# 1_WM-N400MSE.net
KiCad netlist of a schematic drawn in Altium Designer
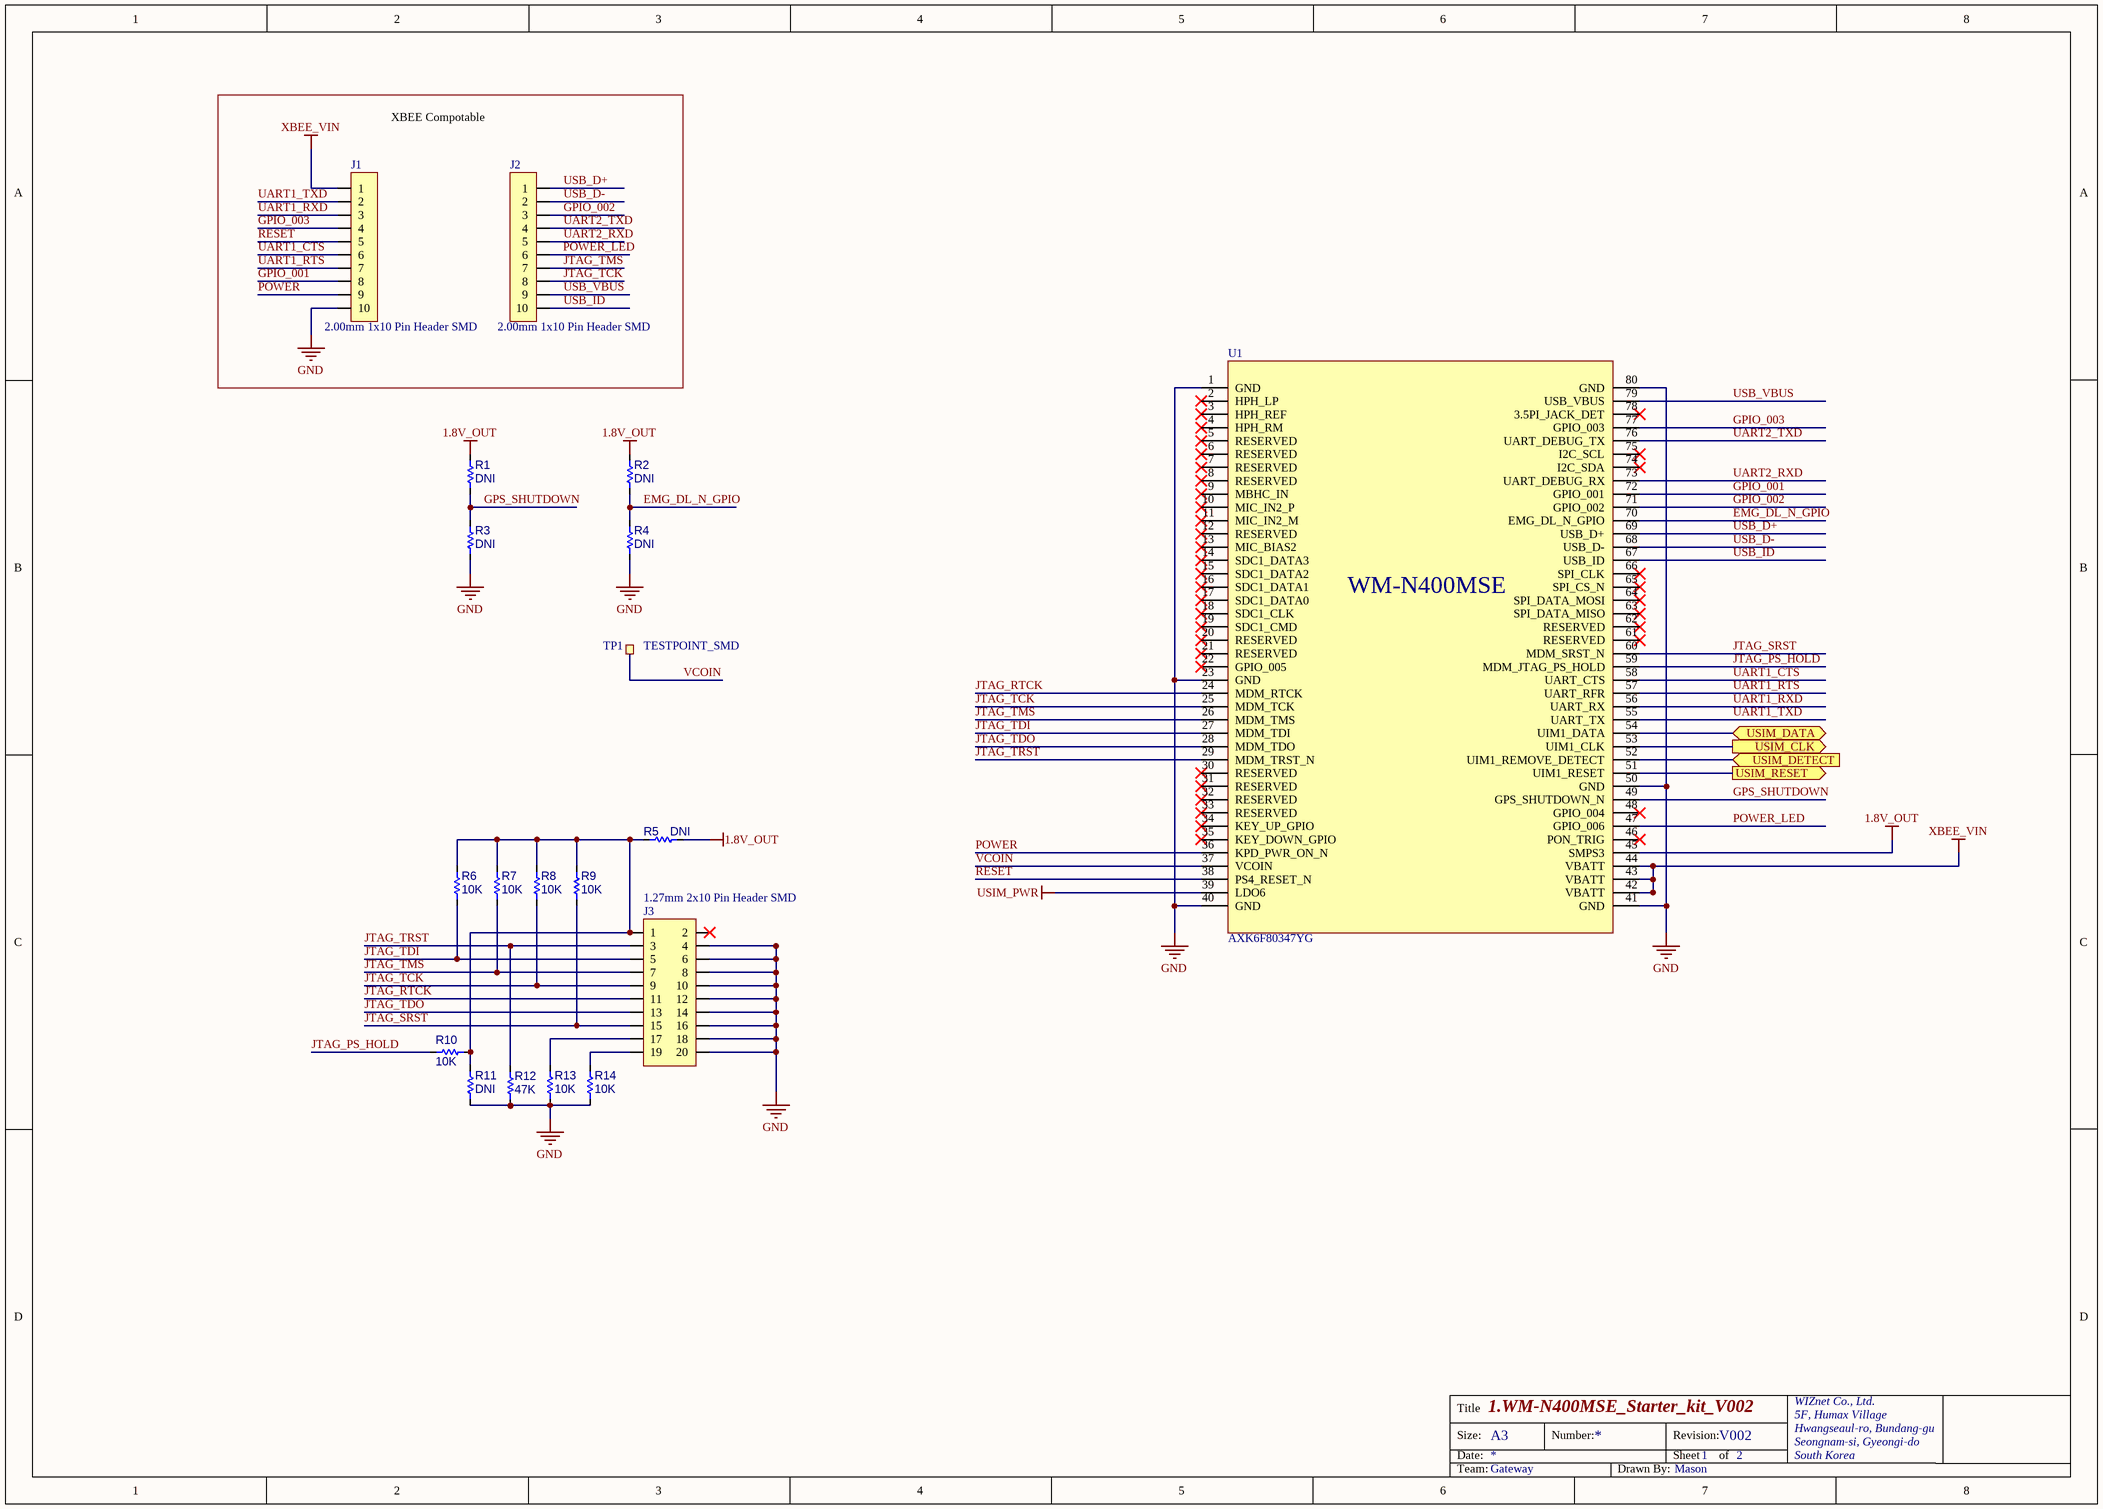
[diagram p0: 1.WM-N400MSE.SchDoc]

(export (version "E")
  (design (tool "Eeschema 10.0.6"))
  (components
    (comp (ref "J1")
      (value "2.00mm 1x10 Pin Header SMD")
      (footprint "IDC(SMD)-1X10(2MM)")
      (libsource (lib "Scott_lib") (part "2.00mm 1x10 Pin Header SMD"))
    )
    (comp (ref "J2")
      (value "2.00mm 1x10 Pin Header SMD")
      (footprint "IDC(SMD)-1X10(2MM)")
      (libsource (lib "") (part "2.00mm 1x10 Pin Header SMD_1"))
    )
    (comp (ref "J3")
      (value "1.27mm 2x10 Pin Header SMD")
      (footprint "IDC(SMD)-2X10(1.27MM)")
      (libsource (lib "Scott_lib") (part "1.27mm 2x10 Pin Header SMD"))
    )
    (comp (ref "R1")
      (value "DNI")
      (footprint "RES-0402")
      (description "RES-0402")
      (libsource (lib "Scott_lib") (part "RES-0402"))
    )
    (comp (ref "R2")
      (value "DNI")
      (footprint "RES-0402")
      (description "RES-0402")
      (libsource (lib "Scott_lib") (part "RES-0402"))
    )
    (comp (ref "R3")
      (value "DNI")
      (footprint "RES-0402")
      (description "RES-0402")
      (libsource (lib "Scott_lib") (part "RES-0402"))
    )
    (comp (ref "R4")
      (value "DNI")
      (footprint "RES-0402")
      (description "RES-0402")
      (libsource (lib "Scott_lib") (part "RES-0402"))
    )
    (comp (ref "R5")
      (value "DNI")
      (footprint "RES-0402")
      (description "RES-0402")
      (libsource (lib "Scott_lib") (part "RES-0402"))
    )
    (comp (ref "R6")
      (value "10K")
      (footprint "RES-0402")
      (description "RES-0402")
      (libsource (lib "Scott_lib") (part "RES-0402"))
    )
    (comp (ref "R7")
      (value "10K")
      (footprint "RES-0402")
      (description "RES-0402")
      (libsource (lib "Scott_lib") (part "RES-0402"))
    )
    (comp (ref "R8")
      (value "10K")
      (footprint "RES-0402")
      (description "RES-0402")
      (libsource (lib "Scott_lib") (part "RES-0402"))
    )
    (comp (ref "R9")
      (value "10K")
      (footprint "RES-0402")
      (description "RES-0402")
      (libsource (lib "Scott_lib") (part "RES-0402"))
    )
    (comp (ref "R10")
      (value "10K")
      (footprint "RES-0402")
      (description "RES-0402")
      (libsource (lib "Scott_lib") (part "RES-0402"))
    )
    (comp (ref "R11")
      (value "DNI")
      (footprint "RES-0402")
      (description "RES-0402")
      (libsource (lib "Scott_lib") (part "RES-0402"))
    )
    (comp (ref "R12")
      (value "47K")
      (footprint "RES-0402")
      (description "RES-0402")
      (libsource (lib "Scott_lib") (part "RES-0402"))
    )
    (comp (ref "R13")
      (value "10K")
      (footprint "RES-0402")
      (description "RES-0402")
      (libsource (lib "Scott_lib") (part "RES-0402"))
    )
    (comp (ref "R14")
      (value "10K")
      (footprint "RES-0402")
      (description "RES-0402")
      (libsource (lib "Scott_lib") (part "RES-0402"))
    )
    (comp (ref "TP1")
      (value "TESTPOINT_SMD")
      (footprint "TP(SMD)-1PI")
      (description "TEST POINT")
      (libsource (lib "Scott_lib") (part "TESTPOINT_SMD"))
    )
    (comp (ref "U1")
      (value "AXK6F80347YG")
      (footprint "WM-N400MSE")
      (description "WM-N400MSE")
      (libsource (lib "Mason_lib") (part "WM-N400MSE"))
    )
  )
  (nets
    (net (code "1") (name "/EMG_DL_N_GPIO") (class "Default")
      (node (ref "R2") (pin "1") (pinfunction "1_1") (pintype "passive"))
      (node (ref "R4") (pin "2") (pinfunction "2_2") (pintype "passive"))
      (node (ref "U1") (pin "70") (pinfunction "EMG_DL_N_GPIO_70") (pintype "passive"))
    )
    (net (code "2") (name "/GPIO_001") (class "Default")
      (node (ref "J1") (pin "8") (pinfunction "8_8") (pintype "passive"))
      (node (ref "U1") (pin "72") (pinfunction "GPIO_001_72") (pintype "passive"))
    )
    (net (code "3") (name "/GPIO_002") (class "Default")
      (node (ref "J2") (pin "3") (pinfunction "3_3") (pintype "passive"))
      (node (ref "U1") (pin "71") (pinfunction "GPIO_002_71") (pintype "passive"))
    )
    (net (code "4") (name "/GPIO_003") (class "Default")
      (node (ref "J1") (pin "4") (pinfunction "4_4") (pintype "passive"))
      (node (ref "U1") (pin "77") (pinfunction "GPIO_003_77") (pintype "passive"))
    )
    (net (code "5") (name "/GPS_SHUTDOWN") (class "Default")
      (node (ref "R1") (pin "1") (pinfunction "1_1") (pintype "passive"))
      (node (ref "R3") (pin "2") (pinfunction "2_2") (pintype "passive"))
      (node (ref "U1") (pin "49") (pinfunction "GPS_SHUTDOWN_N_49") (pintype "passive"))
    )
    (net (code "6") (name "/JTAG_PS_HOLD") (class "Default")
      (node (ref "R10") (pin "2") (pinfunction "2_2") (pintype "passive"))
      (node (ref "U1") (pin "59") (pinfunction "MDM_JTAG_PS_HOLD_59") (pintype "passive"))
    )
    (net (code "7") (name "/JTAG_RTCK") (class "Default")
      (node (ref "J3") (pin "11") (pinfunction "11_11") (pintype "passive"))
      (node (ref "U1") (pin "24") (pinfunction "MDM_RTCK_24") (pintype "passive"))
    )
    (net (code "8") (name "/JTAG_SRST") (class "Default")
      (node (ref "J3") (pin "15") (pinfunction "15_15") (pintype "passive"))
      (node (ref "R9") (pin "1") (pinfunction "1_1") (pintype "passive"))
      (node (ref "U1") (pin "60") (pinfunction "MDM_SRST_N_60") (pintype "passive"))
    )
    (net (code "9") (name "/JTAG_TCK") (class "Default")
      (node (ref "J2") (pin "8") (pinfunction "8_8") (pintype "passive"))
      (node (ref "J3") (pin "9") (pinfunction "9_9") (pintype "passive"))
      (node (ref "R8") (pin "1") (pinfunction "1_1") (pintype "passive"))
      (node (ref "U1") (pin "25") (pinfunction "MDM_TCK_25") (pintype "passive"))
    )
    (net (code "10") (name "/JTAG_TDI") (class "Default")
      (node (ref "J3") (pin "5") (pinfunction "5_5") (pintype "passive"))
      (node (ref "R6") (pin "1") (pinfunction "1_1") (pintype "passive"))
      (node (ref "U1") (pin "27") (pinfunction "MDM_TDI_27") (pintype "passive"))
    )
    (net (code "11") (name "/JTAG_TDO") (class "Default")
      (node (ref "J3") (pin "13") (pinfunction "13_13") (pintype "passive"))
      (node (ref "U1") (pin "28") (pinfunction "MDM_TDO_28") (pintype "passive"))
    )
    (net (code "12") (name "/JTAG_TMS") (class "Default")
      (node (ref "J2") (pin "7") (pinfunction "7_7") (pintype "passive"))
      (node (ref "J3") (pin "7") (pinfunction "7_7") (pintype "passive"))
      (node (ref "R7") (pin "1") (pinfunction "1_1") (pintype "passive"))
      (node (ref "U1") (pin "26") (pinfunction "MDM_TMS_26") (pintype "passive"))
    )
    (net (code "13") (name "/JTAG_TRST") (class "Default")
      (node (ref "J3") (pin "3") (pinfunction "3_3") (pintype "passive"))
      (node (ref "R12") (pin "2") (pinfunction "2_2") (pintype "passive"))
      (node (ref "U1") (pin "29") (pinfunction "MDM_TRST_N_29") (pintype "passive"))
    )
    (net (code "14") (name "/POWER") (class "Default")
      (node (ref "J1") (pin "9") (pinfunction "9_9") (pintype "passive"))
      (node (ref "U1") (pin "36") (pinfunction "KPD_PWR_ON_N_36") (pintype "passive"))
    )
    (net (code "15") (name "/POWER_LED") (class "Default")
      (node (ref "J2") (pin "6") (pinfunction "6_6") (pintype "passive"))
      (node (ref "U1") (pin "47") (pinfunction "GPIO_006_47") (pintype "passive"))
    )
    (net (code "16") (name "/RESET") (class "Default")
      (node (ref "J1") (pin "5") (pinfunction "5_5") (pintype "passive"))
      (node (ref "U1") (pin "38") (pinfunction "PS4_RESET_N_38") (pintype "passive"))
    )
    (net (code "17") (name "/UART1_CTS") (class "Default")
      (node (ref "J1") (pin "6") (pinfunction "6_6") (pintype "passive"))
      (node (ref "U1") (pin "58") (pinfunction "UART_CTS_58") (pintype "passive"))
    )
    (net (code "18") (name "/UART1_RTS") (class "Default")
      (node (ref "J1") (pin "7") (pinfunction "7_7") (pintype "passive"))
      (node (ref "U1") (pin "57") (pinfunction "UART_RFR_57") (pintype "passive"))
    )
    (net (code "19") (name "/UART1_RXD") (class "Default")
      (node (ref "J1") (pin "3") (pinfunction "3_3") (pintype "passive"))
      (node (ref "U1") (pin "56") (pinfunction "UART_RX_56") (pintype "passive"))
    )
    (net (code "20") (name "/UART1_TXD") (class "Default")
      (node (ref "J1") (pin "2") (pinfunction "2_2") (pintype "passive"))
      (node (ref "U1") (pin "55") (pinfunction "UART_TX_55") (pintype "passive"))
    )
    (net (code "21") (name "/UART2_RXD") (class "Default")
      (node (ref "J2") (pin "5") (pinfunction "5_5") (pintype "passive"))
      (node (ref "U1") (pin "73") (pinfunction "UART_DEBUG_RX_73") (pintype "passive"))
    )
    (net (code "22") (name "/UART2_TXD") (class "Default")
      (node (ref "J2") (pin "4") (pinfunction "4_4") (pintype "passive"))
      (node (ref "U1") (pin "76") (pinfunction "UART_DEBUG_TX_76") (pintype "passive"))
    )
    (net (code "23") (name "/USB_D+") (class "Default")
      (node (ref "J2") (pin "1") (pinfunction "1_1") (pintype "passive"))
      (node (ref "U1") (pin "69") (pinfunction "USB_D+_69") (pintype "passive"))
    )
    (net (code "24") (name "/USB_D-") (class "Default")
      (node (ref "J2") (pin "2") (pinfunction "2_2") (pintype "passive"))
      (node (ref "U1") (pin "68") (pinfunction "USB_D-_68") (pintype "passive"))
    )
    (net (code "25") (name "/USB_ID") (class "Default")
      (node (ref "J2") (pin "10") (pinfunction "10_10") (pintype "passive"))
      (node (ref "U1") (pin "67") (pinfunction "USB_ID_67") (pintype "passive"))
    )
    (net (code "26") (name "/USB_VBUS") (class "Default")
      (node (ref "J2") (pin "9") (pinfunction "9_9") (pintype "passive"))
      (node (ref "U1") (pin "79") (pinfunction "USB_VBUS_79") (pintype "passive"))
    )
    (net (code "27") (name "/USIM_CLK") (class "Default")
      (node (ref "U1") (pin "53") (pinfunction "UIM1_CLK_53") (pintype "passive"))
    )
    (net (code "28") (name "/USIM_DATA") (class "Default")
      (node (ref "U1") (pin "54") (pinfunction "UIM1_DATA_54") (pintype "passive"))
    )
    (net (code "29") (name "/USIM_DETECT") (class "Default")
      (node (ref "U1") (pin "52") (pinfunction "UIM1_REMOVE_DETECT_52") (pintype "passive"))
    )
    (net (code "30") (name "/USIM_RESET") (class "Default")
      (node (ref "U1") (pin "51") (pinfunction "UIM1_RESET_51") (pintype "passive"))
    )
    (net (code "31") (name "/VCOIN") (class "Default")
      (node (ref "TP1") (pin "1") (pinfunction "TETSPOINT_1") (pintype "passive"))
      (node (ref "U1") (pin "37") (pinfunction "VCOIN_37") (pintype "passive"))
    )
    (net (code "32") (name "1.8V_OUT") (class "Default")
      (node (ref "R1") (pin "2") (pinfunction "2_2") (pintype "passive"))
      (node (ref "R2") (pin "2") (pinfunction "2_2") (pintype "passive"))
      (node (ref "R5") (pin "1") (pinfunction "1_1") (pintype "passive"))
      (node (ref "U1") (pin "45") (pinfunction "SMPS3_45") (pintype "passive"))
    )
    (net (code "33") (name "GND") (class "Default")
      (node (ref "J1") (pin "10") (pinfunction "10_10") (pintype "passive"))
      (node (ref "J3") (pin "10") (pinfunction "10_10") (pintype "passive"))
      (node (ref "J3") (pin "12") (pinfunction "12_12") (pintype "passive"))
      (node (ref "J3") (pin "14") (pinfunction "14_14") (pintype "passive"))
      (node (ref "J3") (pin "16") (pinfunction "16_16") (pintype "passive"))
      (node (ref "J3") (pin "18") (pinfunction "18_18") (pintype "passive"))
      (node (ref "J3") (pin "20") (pinfunction "20_20") (pintype "passive"))
      (node (ref "J3") (pin "4") (pinfunction "4_4") (pintype "passive"))
      (node (ref "J3") (pin "6") (pinfunction "6_6") (pintype "passive"))
      (node (ref "J3") (pin "8") (pinfunction "8_8") (pintype "passive"))
      (node (ref "R11") (pin "1") (pinfunction "1_1") (pintype "passive"))
      (node (ref "R12") (pin "1") (pinfunction "1_1") (pintype "passive"))
      (node (ref "R13") (pin "1") (pinfunction "1_1") (pintype "passive"))
      (node (ref "R14") (pin "1") (pinfunction "1_1") (pintype "passive"))
      (node (ref "R3") (pin "1") (pinfunction "1_1") (pintype "passive"))
      (node (ref "R4") (pin "1") (pinfunction "1_1") (pintype "passive"))
      (node (ref "U1") (pin "1") (pinfunction "GND_1") (pintype "passive"))
      (node (ref "U1") (pin "23") (pinfunction "GND_23") (pintype "passive"))
      (node (ref "U1") (pin "40") (pinfunction "GND_40") (pintype "passive"))
      (node (ref "U1") (pin "41") (pinfunction "GND_41") (pintype "passive"))
      (node (ref "U1") (pin "50") (pinfunction "GND_50") (pintype "passive"))
      (node (ref "U1") (pin "80") (pinfunction "GND_80") (pintype "passive"))
    )
    (net (code "34") (name "Net-(J3-Pad1)") (class "Default")
      (node (ref "J3") (pin "1") (pinfunction "1_1") (pintype "passive"))
      (node (ref "R10") (pin "1") (pinfunction "1_1") (pintype "passive"))
      (node (ref "R11") (pin "2") (pinfunction "2_2") (pintype "passive"))
      (node (ref "R5") (pin "2") (pinfunction "2_2") (pintype "passive"))
      (node (ref "R6") (pin "2") (pinfunction "2_2") (pintype "passive"))
      (node (ref "R7") (pin "2") (pinfunction "2_2") (pintype "passive"))
      (node (ref "R8") (pin "2") (pinfunction "2_2") (pintype "passive"))
      (node (ref "R9") (pin "2") (pinfunction "2_2") (pintype "passive"))
    )
    (net (code "35") (name "Net-(J3-Pad17)") (class "Default")
      (node (ref "J3") (pin "17") (pinfunction "17_17") (pintype "passive"))
      (node (ref "R13") (pin "2") (pinfunction "2_2") (pintype "passive"))
    )
    (net (code "36") (name "Net-(J3-Pad19)") (class "Default")
      (node (ref "J3") (pin "19") (pinfunction "19_19") (pintype "passive"))
      (node (ref "R14") (pin "2") (pinfunction "2_2") (pintype "passive"))
    )
    (net (code "37") (name "USIM_PWR") (class "Default")
      (node (ref "U1") (pin "39") (pinfunction "LDO6_39") (pintype "passive"))
    )
    (net (code "38") (name "XBEE_VIN") (class "Default")
      (node (ref "J1") (pin "1") (pinfunction "1_1") (pintype "passive"))
      (node (ref "U1") (pin "42") (pinfunction "VBATT_42") (pintype "passive"))
      (node (ref "U1") (pin "43") (pinfunction "VBATT_43") (pintype "passive"))
      (node (ref "U1") (pin "44") (pinfunction "VBATT_44") (pintype "passive"))
    )
    (net (code "39") (name "unconnected-(J3-Pad2)") (class "Default")
      (node (ref "J3") (pin "2") (pinfunction "2_2") (pintype "passive+no_connect"))
    )
    (net (code "40") (name "unconnected-(U1-3.5PI_JACK_DET-Pad78)") (class "Default")
      (node (ref "U1") (pin "78") (pinfunction "3.5PI_JACK_DET_78") (pintype "passive+no_connect"))
    )
    (net (code "41") (name "unconnected-(U1-GPIO_004-Pad48)") (class "Default")
      (node (ref "U1") (pin "48") (pinfunction "GPIO_004_48") (pintype "passive+no_connect"))
    )
    (net (code "42") (name "unconnected-(U1-GPIO_005-Pad22)") (class "Default")
      (node (ref "U1") (pin "22") (pinfunction "GPIO_005_22") (pintype "passive+no_connect"))
    )
    (net (code "43") (name "unconnected-(U1-HPH_LP-Pad2)") (class "Default")
      (node (ref "U1") (pin "2") (pinfunction "HPH_LP_2") (pintype "passive+no_connect"))
    )
    (net (code "44") (name "unconnected-(U1-HPH_REF-Pad3)") (class "Default")
      (node (ref "U1") (pin "3") (pinfunction "HPH_REF_3") (pintype "passive+no_connect"))
    )
    (net (code "45") (name "unconnected-(U1-HPH_RM-Pad4)") (class "Default")
      (node (ref "U1") (pin "4") (pinfunction "HPH_RM_4") (pintype "passive+no_connect"))
    )
    (net (code "46") (name "unconnected-(U1-I2C_SCL-Pad75)") (class "Default")
      (node (ref "U1") (pin "75") (pinfunction "I2C_SCL_75") (pintype "passive+no_connect"))
    )
    (net (code "47") (name "unconnected-(U1-I2C_SDA-Pad74)") (class "Default")
      (node (ref "U1") (pin "74") (pinfunction "I2C_SDA_74") (pintype "passive+no_connect"))
    )
    (net (code "48") (name "unconnected-(U1-KEY_DOWN_GPIO-Pad35)") (class "Default")
      (node (ref "U1") (pin "35") (pinfunction "KEY_DOWN_GPIO_35") (pintype "passive+no_connect"))
    )
    (net (code "49") (name "unconnected-(U1-KEY_UP_GPIO-Pad34)") (class "Default")
      (node (ref "U1") (pin "34") (pinfunction "KEY_UP_GPIO_34") (pintype "passive+no_connect"))
    )
    (net (code "50") (name "unconnected-(U1-MBHC_IN-Pad9)") (class "Default")
      (node (ref "U1") (pin "9") (pinfunction "MBHC_IN_9") (pintype "passive+no_connect"))
    )
    (net (code "51") (name "unconnected-(U1-MIC_BIAS2-Pad13)") (class "Default")
      (node (ref "U1") (pin "13") (pinfunction "MIC_BIAS2_13") (pintype "passive+no_connect"))
    )
    (net (code "52") (name "unconnected-(U1-MIC_IN2_M-Pad11)") (class "Default")
      (node (ref "U1") (pin "11") (pinfunction "MIC_IN2_M_11") (pintype "passive+no_connect"))
    )
    (net (code "53") (name "unconnected-(U1-MIC_IN2_P-Pad10)") (class "Default")
      (node (ref "U1") (pin "10") (pinfunction "MIC_IN2_P_10") (pintype "passive+no_connect"))
    )
    (net (code "54") (name "unconnected-(U1-PON_TRIG-Pad46)") (class "Default")
      (node (ref "U1") (pin "46") (pinfunction "PON_TRIG_46") (pintype "passive+no_connect"))
    )
    (net (code "55") (name "unconnected-(U1-RESERVED-Pad5)") (class "Default")
      (node (ref "U1") (pin "5") (pinfunction "RESERVED_5") (pintype "passive+no_connect"))
    )
    (net (code "56") (name "unconnected-(U1-RESERVED-Pad6)") (class "Default")
      (node (ref "U1") (pin "6") (pinfunction "RESERVED_6") (pintype "passive+no_connect"))
    )
    (net (code "57") (name "unconnected-(U1-RESERVED-Pad7)") (class "Default")
      (node (ref "U1") (pin "7") (pinfunction "RESERVED_7") (pintype "passive+no_connect"))
    )
    (net (code "58") (name "unconnected-(U1-RESERVED-Pad8)") (class "Default")
      (node (ref "U1") (pin "8") (pinfunction "RESERVED_8") (pintype "passive+no_connect"))
    )
    (net (code "59") (name "unconnected-(U1-RESERVED-Pad12)") (class "Default")
      (node (ref "U1") (pin "12") (pinfunction "RESERVED_12") (pintype "passive+no_connect"))
    )
    (net (code "60") (name "unconnected-(U1-RESERVED-Pad20)") (class "Default")
      (node (ref "U1") (pin "20") (pinfunction "RESERVED_20") (pintype "passive+no_connect"))
    )
    (net (code "61") (name "unconnected-(U1-RESERVED-Pad21)") (class "Default")
      (node (ref "U1") (pin "21") (pinfunction "RESERVED_21") (pintype "passive+no_connect"))
    )
    (net (code "62") (name "unconnected-(U1-RESERVED-Pad30)") (class "Default")
      (node (ref "U1") (pin "30") (pinfunction "RESERVED_30") (pintype "passive+no_connect"))
    )
    (net (code "63") (name "unconnected-(U1-RESERVED-Pad31)") (class "Default")
      (node (ref "U1") (pin "31") (pinfunction "RESERVED_31") (pintype "passive+no_connect"))
    )
    (net (code "64") (name "unconnected-(U1-RESERVED-Pad32)") (class "Default")
      (node (ref "U1") (pin "32") (pinfunction "RESERVED_32") (pintype "passive+no_connect"))
    )
    (net (code "65") (name "unconnected-(U1-RESERVED-Pad33)") (class "Default")
      (node (ref "U1") (pin "33") (pinfunction "RESERVED_33") (pintype "passive+no_connect"))
    )
    (net (code "66") (name "unconnected-(U1-RESERVED-Pad61)") (class "Default")
      (node (ref "U1") (pin "61") (pinfunction "RESERVED_61") (pintype "passive+no_connect"))
    )
    (net (code "67") (name "unconnected-(U1-RESERVED-Pad62)") (class "Default")
      (node (ref "U1") (pin "62") (pinfunction "RESERVED_62") (pintype "passive+no_connect"))
    )
    (net (code "68") (name "unconnected-(U1-SDC1_CLK-Pad18)") (class "Default")
      (node (ref "U1") (pin "18") (pinfunction "SDC1_CLK_18") (pintype "passive+no_connect"))
    )
    (net (code "69") (name "unconnected-(U1-SDC1_CMD-Pad19)") (class "Default")
      (node (ref "U1") (pin "19") (pinfunction "SDC1_CMD_19") (pintype "passive+no_connect"))
    )
    (net (code "70") (name "unconnected-(U1-SDC1_DATA0-Pad17)") (class "Default")
      (node (ref "U1") (pin "17") (pinfunction "SDC1_DATA0_17") (pintype "passive+no_connect"))
    )
    (net (code "71") (name "unconnected-(U1-SDC1_DATA1-Pad16)") (class "Default")
      (node (ref "U1") (pin "16") (pinfunction "SDC1_DATA1_16") (pintype "passive+no_connect"))
    )
    (net (code "72") (name "unconnected-(U1-SDC1_DATA2-Pad15)") (class "Default")
      (node (ref "U1") (pin "15") (pinfunction "SDC1_DATA2_15") (pintype "passive+no_connect"))
    )
    (net (code "73") (name "unconnected-(U1-SDC1_DATA3-Pad14)") (class "Default")
      (node (ref "U1") (pin "14") (pinfunction "SDC1_DATA3_14") (pintype "passive+no_connect"))
    )
    (net (code "74") (name "unconnected-(U1-SPI_CLK-Pad66)") (class "Default")
      (node (ref "U1") (pin "66") (pinfunction "SPI_CLK_66") (pintype "passive+no_connect"))
    )
    (net (code "75") (name "unconnected-(U1-SPI_CS_N-Pad65)") (class "Default")
      (node (ref "U1") (pin "65") (pinfunction "SPI_CS_N_65") (pintype "passive+no_connect"))
    )
    (net (code "76") (name "unconnected-(U1-SPI_DATA_MISO-Pad63)") (class "Default")
      (node (ref "U1") (pin "63") (pinfunction "SPI_DATA_MISO_63") (pintype "passive+no_connect"))
    )
    (net (code "77") (name "unconnected-(U1-SPI_DATA_MOSI-Pad64)") (class "Default")
      (node (ref "U1") (pin "64") (pinfunction "SPI_DATA_MOSI_64") (pintype "passive+no_connect"))
    )
  )
)
